# Sheet1.net
KiCad netlist of a schematic drawn in Altium Designer
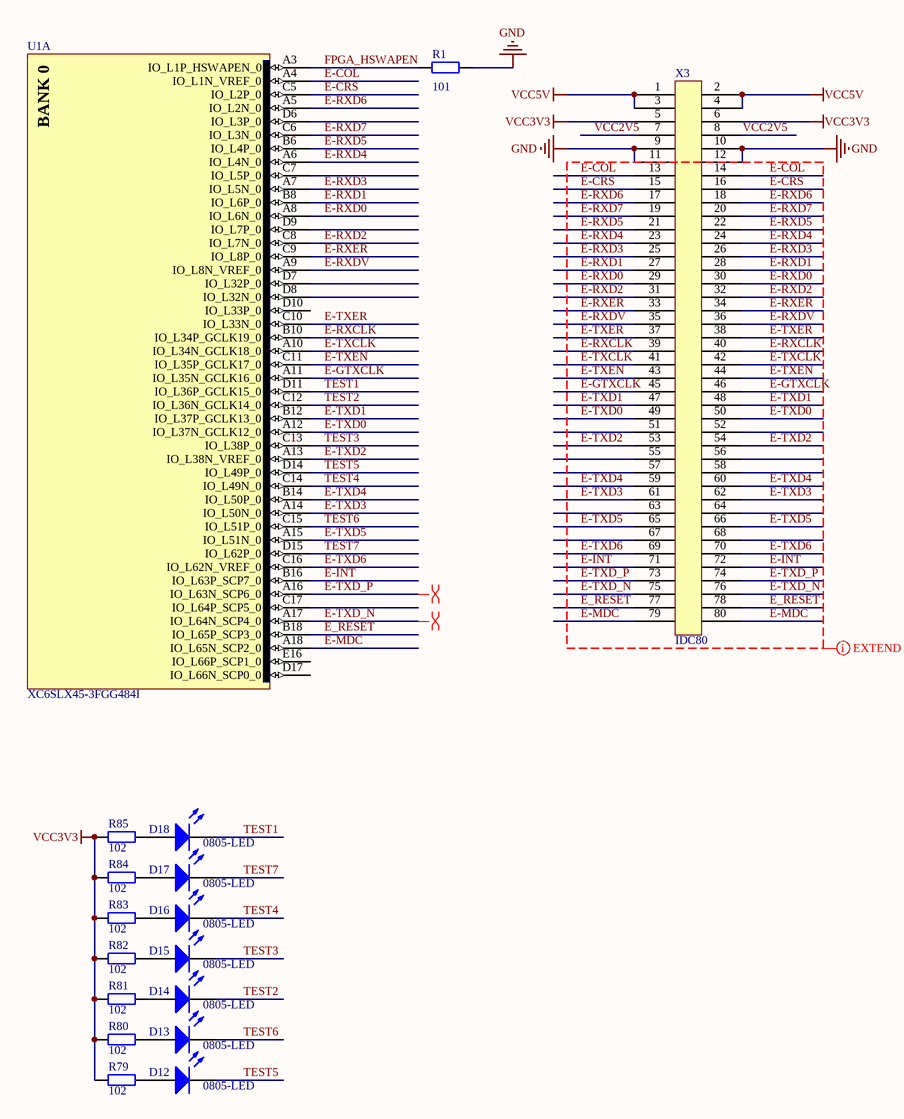
[diagram p0: Sheet1.SchDoc]

(export (version "E")
  (design (tool "Eeschema 10.0.6"))
  (components
    (comp (ref "D12")
      (value "0805-LED")
      (footprint "0805LED")
      (description "Typical INFRARED GaAs LED")
      (fields (field (name "PUBLISHER") "Altium Limited"))
      (libsource (lib "Miscellaneous Devices") (part "LED0"))
    )
    (comp (ref "D13")
      (value "0805-LED")
      (footprint "0805LED")
      (description "Typical INFRARED GaAs LED")
      (fields (field (name "PUBLISHER") "Altium Limited"))
      (libsource (lib "Miscellaneous Devices") (part "LED0"))
    )
    (comp (ref "D14")
      (value "0805-LED")
      (footprint "0805LED")
      (description "Typical INFRARED GaAs LED")
      (fields (field (name "PUBLISHER") "Altium Limited"))
      (libsource (lib "Miscellaneous Devices") (part "LED0"))
    )
    (comp (ref "D15")
      (value "0805-LED")
      (footprint "0805LED")
      (description "Typical INFRARED GaAs LED")
      (fields (field (name "PUBLISHER") "Altium Limited"))
      (libsource (lib "Miscellaneous Devices") (part "LED0"))
    )
    (comp (ref "D16")
      (value "0805-LED")
      (footprint "0805LED")
      (description "Typical INFRARED GaAs LED")
      (fields (field (name "PUBLISHER") "Altium Limited"))
      (libsource (lib "Miscellaneous Devices") (part "LED0"))
    )
    (comp (ref "D17")
      (value "0805-LED")
      (footprint "0805LED")
      (description "Typical INFRARED GaAs LED")
      (fields (field (name "PUBLISHER") "Altium Limited"))
      (libsource (lib "Miscellaneous Devices") (part "LED0"))
    )
    (comp (ref "D18")
      (value "0805-LED")
      (footprint "0805LED")
      (description "Typical INFRARED GaAs LED")
      (fields (field (name "PUBLISHER") "Altium Limited"))
      (libsource (lib "Miscellaneous Devices") (part "LED0"))
    )
    (comp (ref "R1")
      (value "101")
      (footprint "0603")
      (description "Resistor")
      (fields (field (name "PUBLISHER") "Altium Limited"))
      (libsource (lib "Miscellaneous Devices") (part "Res2"))
    )
    (comp (ref "R79")
      (value "102")
      (footprint "0603")
      (description "Resistor")
      (fields (field (name "PUBLISHER") "Altium Limited"))
      (libsource (lib "") (part "Res2_1"))
    )
    (comp (ref "R80")
      (value "102")
      (footprint "0603")
      (description "Resistor")
      (fields (field (name "PUBLISHER") "Altium Limited"))
      (libsource (lib "") (part "Res2_1"))
    )
    (comp (ref "R81")
      (value "102")
      (footprint "0603")
      (description "Resistor")
      (fields (field (name "PUBLISHER") "Altium Limited"))
      (libsource (lib "") (part "Res2_1"))
    )
    (comp (ref "R82")
      (value "102")
      (footprint "0603")
      (description "Resistor")
      (fields (field (name "PUBLISHER") "Altium Limited"))
      (libsource (lib "") (part "Res2_1"))
    )
    (comp (ref "R83")
      (value "102")
      (footprint "0603")
      (description "Resistor")
      (fields (field (name "PUBLISHER") "Altium Limited"))
      (libsource (lib "") (part "Res2_1"))
    )
    (comp (ref "R84")
      (value "102")
      (footprint "0603")
      (description "Resistor")
      (fields (field (name "PUBLISHER") "Altium Limited"))
      (libsource (lib "") (part "Res2_1"))
    )
    (comp (ref "R85")
      (value "102")
      (footprint "0603")
      (description "Resistor")
      (fields (field (name "PUBLISHER") "Altium Limited"))
      (libsource (lib "") (part "Res2_1"))
    )
    (comp (ref "U1")
      (value "XC6SLX45-3FGG484I")
      (footprint "FGG484")
      (fields (field (name "PUBLISHER") "Altium Limited"))
      (libsource (lib "Xilinx Spartan-6") (part "XC6SLX45-3FGG484I"))
    )
    (comp (ref "X3")
      (value "IDC80")
      (footprint "SDC80_1.27MM_MALE")
      (libsource (lib "Schlib1") (part "IDC80"))
    )
  )
  (nets
    (net (code "1") (name "/E-COL") (class "Default")
      (node (ref "U1") (pin "A4") (pinfunction "IO_L1N_VREF_0_A4") (pintype "bidirectional"))
      (node (ref "X3") (pin "13") (pinfunction "13_13") (pintype "passive"))
      (node (ref "X3") (pin "14") (pinfunction "14_14") (pintype "passive"))
    )
    (net (code "2") (name "/E-CRS") (class "Default")
      (node (ref "U1") (pin "C5") (pinfunction "IO_L2P_0_C5") (pintype "bidirectional"))
      (node (ref "X3") (pin "15") (pinfunction "15_15") (pintype "passive"))
      (node (ref "X3") (pin "16") (pinfunction "16_16") (pintype "passive"))
    )
    (net (code "3") (name "/E-GTXCLK") (class "Default")
      (node (ref "U1") (pin "A11") (pinfunction "IO_L35N_GCLK16_0_A11") (pintype "bidirectional"))
      (node (ref "X3") (pin "45") (pinfunction "45_45") (pintype "passive"))
      (node (ref "X3") (pin "46") (pinfunction "46_46") (pintype "passive"))
    )
    (net (code "4") (name "/E-INT") (class "Default")
      (node (ref "U1") (pin "B16") (pinfunction "IO_L63P_SCP7_0_B16") (pintype "bidirectional"))
      (node (ref "X3") (pin "71") (pinfunction "71_71") (pintype "passive"))
      (node (ref "X3") (pin "72") (pinfunction "72_72") (pintype "passive"))
    )
    (net (code "5") (name "/E-MDC") (class "Default")
      (node (ref "U1") (pin "A18") (pinfunction "IO_L65N_SCP2_0_A18") (pintype "bidirectional"))
      (node (ref "X3") (pin "79") (pinfunction "79_79") (pintype "passive"))
      (node (ref "X3") (pin "80") (pinfunction "80_80") (pintype "passive"))
    )
    (net (code "6") (name "/E-RXCLK") (class "Default")
      (node (ref "U1") (pin "B10") (pinfunction "IO_L34P_GCLK19_0_B10") (pintype "bidirectional"))
      (node (ref "X3") (pin "39") (pinfunction "39_39") (pintype "passive"))
      (node (ref "X3") (pin "40") (pinfunction "40_40") (pintype "passive"))
    )
    (net (code "7") (name "/E-RXD0") (class "Default")
      (node (ref "U1") (pin "A8") (pinfunction "IO_L6N_0_A8") (pintype "bidirectional"))
      (node (ref "X3") (pin "29") (pinfunction "29_29") (pintype "passive"))
      (node (ref "X3") (pin "30") (pinfunction "30_30") (pintype "passive"))
    )
    (net (code "8") (name "/E-RXD1") (class "Default")
      (node (ref "U1") (pin "B8") (pinfunction "IO_L6P_0_B8") (pintype "bidirectional"))
      (node (ref "X3") (pin "27") (pinfunction "27_27") (pintype "passive"))
      (node (ref "X3") (pin "28") (pinfunction "28_28") (pintype "passive"))
    )
    (net (code "9") (name "/E-RXD2") (class "Default")
      (node (ref "U1") (pin "C8") (pinfunction "IO_L7N_0_C8") (pintype "bidirectional"))
      (node (ref "X3") (pin "31") (pinfunction "31_31") (pintype "passive"))
      (node (ref "X3") (pin "32") (pinfunction "32_32") (pintype "passive"))
    )
    (net (code "10") (name "/E-RXD3") (class "Default")
      (node (ref "U1") (pin "A7") (pinfunction "IO_L5N_0_A7") (pintype "bidirectional"))
      (node (ref "X3") (pin "25") (pinfunction "25_25") (pintype "passive"))
      (node (ref "X3") (pin "26") (pinfunction "26_26") (pintype "passive"))
    )
    (net (code "11") (name "/E-RXD4") (class "Default")
      (node (ref "U1") (pin "A6") (pinfunction "IO_L4N_0_A6") (pintype "bidirectional"))
      (node (ref "X3") (pin "23") (pinfunction "23_23") (pintype "passive"))
      (node (ref "X3") (pin "24") (pinfunction "24_24") (pintype "passive"))
    )
    (net (code "12") (name "/E-RXD5") (class "Default")
      (node (ref "U1") (pin "B6") (pinfunction "IO_L4P_0_B6") (pintype "bidirectional"))
      (node (ref "X3") (pin "21") (pinfunction "21_21") (pintype "passive"))
      (node (ref "X3") (pin "22") (pinfunction "22_22") (pintype "passive"))
    )
    (net (code "13") (name "/E-RXD6") (class "Default")
      (node (ref "U1") (pin "A5") (pinfunction "IO_L2N_0_A5") (pintype "bidirectional"))
      (node (ref "X3") (pin "17") (pinfunction "17_17") (pintype "passive"))
      (node (ref "X3") (pin "18") (pinfunction "18_18") (pintype "passive"))
    )
    (net (code "14") (name "/E-RXD7") (class "Default")
      (node (ref "U1") (pin "C6") (pinfunction "IO_L3N_0_C6") (pintype "bidirectional"))
      (node (ref "X3") (pin "19") (pinfunction "19_19") (pintype "passive"))
      (node (ref "X3") (pin "20") (pinfunction "20_20") (pintype "passive"))
    )
    (net (code "15") (name "/E-RXDV") (class "Default")
      (node (ref "U1") (pin "A9") (pinfunction "IO_L8N_VREF_0_A9") (pintype "bidirectional"))
      (node (ref "X3") (pin "35") (pinfunction "35_35") (pintype "passive"))
      (node (ref "X3") (pin "36") (pinfunction "36_36") (pintype "passive"))
    )
    (net (code "16") (name "/E-RXER") (class "Default")
      (node (ref "U1") (pin "C9") (pinfunction "IO_L8P_0_C9") (pintype "bidirectional"))
      (node (ref "X3") (pin "33") (pinfunction "33_33") (pintype "passive"))
      (node (ref "X3") (pin "34") (pinfunction "34_34") (pintype "passive"))
    )
    (net (code "17") (name "/E-TXCLK") (class "Default")
      (node (ref "U1") (pin "A10") (pinfunction "IO_L34N_GCLK18_0_A10") (pintype "bidirectional"))
      (node (ref "X3") (pin "41") (pinfunction "41_41") (pintype "passive"))
      (node (ref "X3") (pin "42") (pinfunction "42_42") (pintype "passive"))
    )
    (net (code "18") (name "/E-TXD0") (class "Default")
      (node (ref "U1") (pin "A12") (pinfunction "IO_L37N_GCLK12_0_A12") (pintype "bidirectional"))
      (node (ref "X3") (pin "49") (pinfunction "49_49") (pintype "passive"))
      (node (ref "X3") (pin "50") (pinfunction "50_50") (pintype "passive"))
    )
    (net (code "19") (name "/E-TXD1") (class "Default")
      (node (ref "U1") (pin "B12") (pinfunction "IO_L37P_GCLK13_0_B12") (pintype "bidirectional"))
      (node (ref "X3") (pin "47") (pinfunction "47_47") (pintype "passive"))
      (node (ref "X3") (pin "48") (pinfunction "48_48") (pintype "passive"))
    )
    (net (code "20") (name "/E-TXD2") (class "Default")
      (node (ref "U1") (pin "A13") (pinfunction "IO_L38N_VREF_0_A13") (pintype "bidirectional"))
      (node (ref "X3") (pin "53") (pinfunction "53_53") (pintype "passive"))
      (node (ref "X3") (pin "54") (pinfunction "54_54") (pintype "passive"))
    )
    (net (code "21") (name "/E-TXD3") (class "Default")
      (node (ref "U1") (pin "A14") (pinfunction "IO_L50N_0_A14") (pintype "bidirectional"))
      (node (ref "X3") (pin "61") (pinfunction "61_61") (pintype "passive"))
      (node (ref "X3") (pin "62") (pinfunction "62_62") (pintype "passive"))
    )
    (net (code "22") (name "/E-TXD4") (class "Default")
      (node (ref "U1") (pin "B14") (pinfunction "IO_L50P_0_B14") (pintype "bidirectional"))
      (node (ref "X3") (pin "59") (pinfunction "59_59") (pintype "passive"))
      (node (ref "X3") (pin "60") (pinfunction "60_60") (pintype "passive"))
    )
    (net (code "23") (name "/E-TXD5") (class "Default")
      (node (ref "U1") (pin "A15") (pinfunction "IO_L51N_0_A15") (pintype "bidirectional"))
      (node (ref "X3") (pin "65") (pinfunction "65_65") (pintype "passive"))
      (node (ref "X3") (pin "66") (pinfunction "66_66") (pintype "passive"))
    )
    (net (code "24") (name "/E-TXD6") (class "Default")
      (node (ref "U1") (pin "C16") (pinfunction "IO_L62N_VREF_0_C16") (pintype "bidirectional"))
      (node (ref "X3") (pin "69") (pinfunction "69_69") (pintype "passive"))
      (node (ref "X3") (pin "70") (pinfunction "70_70") (pintype "passive"))
    )
    (net (code "25") (name "/E-TXD_N") (class "Default")
      (node (ref "U1") (pin "A17") (pinfunction "IO_L64N_SCP4_0_A17") (pintype "bidirectional"))
      (node (ref "X3") (pin "75") (pinfunction "75_75") (pintype "passive"))
      (node (ref "X3") (pin "76") (pinfunction "76_76") (pintype "passive"))
    )
    (net (code "26") (name "/E-TXD_P") (class "Default")
      (node (ref "U1") (pin "A16") (pinfunction "IO_L63N_SCP6_0_A16") (pintype "bidirectional"))
      (node (ref "X3") (pin "73") (pinfunction "73_73") (pintype "passive"))
      (node (ref "X3") (pin "74") (pinfunction "74_74") (pintype "passive"))
    )
    (net (code "27") (name "/E-TXEN") (class "Default")
      (node (ref "U1") (pin "C11") (pinfunction "IO_L35P_GCLK17_0_C11") (pintype "bidirectional"))
      (node (ref "X3") (pin "43") (pinfunction "43_43") (pintype "passive"))
      (node (ref "X3") (pin "44") (pinfunction "44_44") (pintype "passive"))
    )
    (net (code "28") (name "/E-TXER") (class "Default")
      (node (ref "U1") (pin "C10") (pinfunction "IO_L33N_0_C10") (pintype "bidirectional"))
      (node (ref "X3") (pin "37") (pinfunction "37_37") (pintype "passive"))
      (node (ref "X3") (pin "38") (pinfunction "38_38") (pintype "passive"))
    )
    (net (code "29") (name "/E_RESET") (class "Default")
      (node (ref "U1") (pin "B18") (pinfunction "IO_L65P_SCP3_0_B18") (pintype "bidirectional"))
      (node (ref "X3") (pin "77") (pinfunction "77_77") (pintype "passive"))
      (node (ref "X3") (pin "78") (pinfunction "78_78") (pintype "passive"))
    )
    (net (code "30") (name "/FPGA_HSWAPEN") (class "Default")
      (node (ref "R1") (pin "2") (pinfunction "2_2") (pintype "passive"))
      (node (ref "U1") (pin "A3") (pinfunction "IO_L1P_HSWAPEN_0_A3") (pintype "bidirectional"))
    )
    (net (code "31") (name "/TEST1") (class "Default")
      (node (ref "D18") (pin "2") (pinfunction "K_2") (pintype "passive"))
      (node (ref "U1") (pin "D11") (pinfunction "IO_L36P_GCLK15_0_D11") (pintype "bidirectional"))
    )
    (net (code "32") (name "/TEST2") (class "Default")
      (node (ref "D14") (pin "2") (pinfunction "K_2") (pintype "passive"))
      (node (ref "U1") (pin "C12") (pinfunction "IO_L36N_GCLK14_0_C12") (pintype "bidirectional"))
    )
    (net (code "33") (name "/TEST3") (class "Default")
      (node (ref "D15") (pin "2") (pinfunction "K_2") (pintype "passive"))
      (node (ref "U1") (pin "C13") (pinfunction "IO_L38P_0_C13") (pintype "bidirectional"))
    )
    (net (code "34") (name "/TEST4") (class "Default")
      (node (ref "D16") (pin "2") (pinfunction "K_2") (pintype "passive"))
      (node (ref "U1") (pin "C14") (pinfunction "IO_L49N_0_C14") (pintype "bidirectional"))
    )
    (net (code "35") (name "/TEST5") (class "Default")
      (node (ref "D12") (pin "2") (pinfunction "K_2") (pintype "passive"))
      (node (ref "U1") (pin "D14") (pinfunction "IO_L49P_0_D14") (pintype "bidirectional"))
    )
    (net (code "36") (name "/TEST6") (class "Default")
      (node (ref "D13") (pin "2") (pinfunction "K_2") (pintype "passive"))
      (node (ref "U1") (pin "C15") (pinfunction "IO_L51P_0_C15") (pintype "bidirectional"))
    )
    (net (code "37") (name "/TEST7") (class "Default")
      (node (ref "D17") (pin "2") (pinfunction "K_2") (pintype "passive"))
      (node (ref "U1") (pin "D15") (pinfunction "IO_L62P_0_D15") (pintype "bidirectional"))
    )
    (net (code "38") (name "/VCC2V5") (class "Default")
      (node (ref "X3") (pin "7") (pinfunction "7_7") (pintype "passive"))
      (node (ref "X3") (pin "8") (pinfunction "8_8") (pintype "passive"))
    )
    (net (code "39") (name "GND") (class "Default")
      (node (ref "R1") (pin "1") (pinfunction "1_1") (pintype "passive"))
      (node (ref "X3") (pin "10") (pinfunction "10_10") (pintype "passive"))
      (node (ref "X3") (pin "11") (pinfunction "11_11") (pintype "passive"))
      (node (ref "X3") (pin "12") (pinfunction "12_12") (pintype "passive"))
      (node (ref "X3") (pin "9") (pinfunction "9_9") (pintype "passive"))
    )
    (net (code "40") (name "Net-(D12-A)") (class "Default")
      (node (ref "D12") (pin "1") (pinfunction "A_1") (pintype "passive"))
      (node (ref "R79") (pin "2") (pinfunction "2_2") (pintype "passive"))
    )
    (net (code "41") (name "Net-(D13-A)") (class "Default")
      (node (ref "D13") (pin "1") (pinfunction "A_1") (pintype "passive"))
      (node (ref "R80") (pin "2") (pinfunction "2_2") (pintype "passive"))
    )
    (net (code "42") (name "Net-(D14-A)") (class "Default")
      (node (ref "D14") (pin "1") (pinfunction "A_1") (pintype "passive"))
      (node (ref "R81") (pin "2") (pinfunction "2_2") (pintype "passive"))
    )
    (net (code "43") (name "Net-(D15-A)") (class "Default")
      (node (ref "D15") (pin "1") (pinfunction "A_1") (pintype "passive"))
      (node (ref "R82") (pin "2") (pinfunction "2_2") (pintype "passive"))
    )
    (net (code "44") (name "Net-(D16-A)") (class "Default")
      (node (ref "D16") (pin "1") (pinfunction "A_1") (pintype "passive"))
      (node (ref "R83") (pin "2") (pinfunction "2_2") (pintype "passive"))
    )
    (net (code "45") (name "Net-(D17-A)") (class "Default")
      (node (ref "D17") (pin "1") (pinfunction "A_1") (pintype "passive"))
      (node (ref "R84") (pin "2") (pinfunction "2_2") (pintype "passive"))
    )
    (net (code "46") (name "Net-(D18-A)") (class "Default")
      (node (ref "D18") (pin "1") (pinfunction "A_1") (pintype "passive"))
      (node (ref "R85") (pin "2") (pinfunction "2_2") (pintype "passive"))
    )
    (net (code "47") (name "VCC3V3") (class "Default")
      (node (ref "R79") (pin "1") (pinfunction "1_1") (pintype "passive"))
      (node (ref "R80") (pin "1") (pinfunction "1_1") (pintype "passive"))
      (node (ref "R81") (pin "1") (pinfunction "1_1") (pintype "passive"))
      (node (ref "R82") (pin "1") (pinfunction "1_1") (pintype "passive"))
      (node (ref "R83") (pin "1") (pinfunction "1_1") (pintype "passive"))
      (node (ref "R84") (pin "1") (pinfunction "1_1") (pintype "passive"))
      (node (ref "R85") (pin "1") (pinfunction "1_1") (pintype "passive"))
      (node (ref "X3") (pin "5") (pinfunction "5_5") (pintype "passive"))
      (node (ref "X3") (pin "6") (pinfunction "6_6") (pintype "passive"))
    )
    (net (code "48") (name "VCC5V") (class "Default")
      (node (ref "X3") (pin "1") (pinfunction "1_1") (pintype "passive"))
      (node (ref "X3") (pin "2") (pinfunction "2_2") (pintype "passive"))
      (node (ref "X3") (pin "3") (pinfunction "3_3") (pintype "passive"))
      (node (ref "X3") (pin "4") (pinfunction "4_4") (pintype "passive"))
    )
    (net (code "49") (name "unconnected-(U1A-IO_L3P_0-PadD6)") (class "Default")
      (node (ref "U1") (pin "D6") (pinfunction "IO_L3P_0_D6") (pintype "bidirectional"))
    )
    (net (code "50") (name "unconnected-(U1A-IO_L5P_0-PadC7)") (class "Default")
      (node (ref "U1") (pin "C7") (pinfunction "IO_L5P_0_C7") (pintype "bidirectional"))
    )
    (net (code "51") (name "unconnected-(U1A-IO_L7P_0-PadD9)") (class "Default")
      (node (ref "U1") (pin "D9") (pinfunction "IO_L7P_0_D9") (pintype "bidirectional"))
    )
    (net (code "52") (name "unconnected-(U1A-IO_L32N_0-PadD8)") (class "Default")
      (node (ref "U1") (pin "D8") (pinfunction "IO_L32N_0_D8") (pintype "bidirectional"))
    )
    (net (code "53") (name "unconnected-(U1A-IO_L32P_0-PadD7)") (class "Default")
      (node (ref "U1") (pin "D7") (pinfunction "IO_L32P_0_D7") (pintype "bidirectional"))
    )
    (net (code "54") (name "unconnected-(U1A-IO_L33P_0-PadD10)") (class "Default")
      (node (ref "U1") (pin "D10") (pinfunction "IO_L33P_0_D10") (pintype "bidirectional"))
    )
    (net (code "55") (name "unconnected-(U1A-IO_L64P_SCP5_0-PadC17)") (class "Default")
      (node (ref "U1") (pin "C17") (pinfunction "IO_L64P_SCP5_0_C17") (pintype "bidirectional"))
    )
    (net (code "56") (name "unconnected-(U1A-IO_L66N_SCP0_0-PadD17)") (class "Default")
      (node (ref "U1") (pin "D17") (pinfunction "IO_L66N_SCP0_0_D17") (pintype "bidirectional"))
    )
    (net (code "57") (name "unconnected-(U1A-IO_L66P_SCP1_0-PadE16)") (class "Default")
      (node (ref "U1") (pin "E16") (pinfunction "IO_L66P_SCP1_0_E16") (pintype "bidirectional"))
    )
    (net (code "58") (name "unconnected-(X3-Pad51)") (class "Default")
      (node (ref "X3") (pin "51") (pinfunction "51_51") (pintype "passive"))
    )
    (net (code "59") (name "unconnected-(X3-Pad52)") (class "Default")
      (node (ref "X3") (pin "52") (pinfunction "52_52") (pintype "passive"))
    )
    (net (code "60") (name "unconnected-(X3-Pad55)") (class "Default")
      (node (ref "X3") (pin "55") (pinfunction "55_55") (pintype "passive"))
    )
    (net (code "61") (name "unconnected-(X3-Pad56)") (class "Default")
      (node (ref "X3") (pin "56") (pinfunction "56_56") (pintype "passive"))
    )
    (net (code "62") (name "unconnected-(X3-Pad57)") (class "Default")
      (node (ref "X3") (pin "57") (pinfunction "57_57") (pintype "passive"))
    )
    (net (code "63") (name "unconnected-(X3-Pad58)") (class "Default")
      (node (ref "X3") (pin "58") (pinfunction "58_58") (pintype "passive"))
    )
    (net (code "64") (name "unconnected-(X3-Pad63)") (class "Default")
      (node (ref "X3") (pin "63") (pinfunction "63_63") (pintype "passive"))
    )
    (net (code "65") (name "unconnected-(X3-Pad64)") (class "Default")
      (node (ref "X3") (pin "64") (pinfunction "64_64") (pintype "passive"))
    )
    (net (code "66") (name "unconnected-(X3-Pad67)") (class "Default")
      (node (ref "X3") (pin "67") (pinfunction "67_67") (pintype "passive"))
    )
    (net (code "67") (name "unconnected-(X3-Pad68)") (class "Default")
      (node (ref "X3") (pin "68") (pinfunction "68_68") (pintype "passive"))
    )
  )
)
